# power_28V.net
KiCad netlist of a schematic drawn in Altium Designer
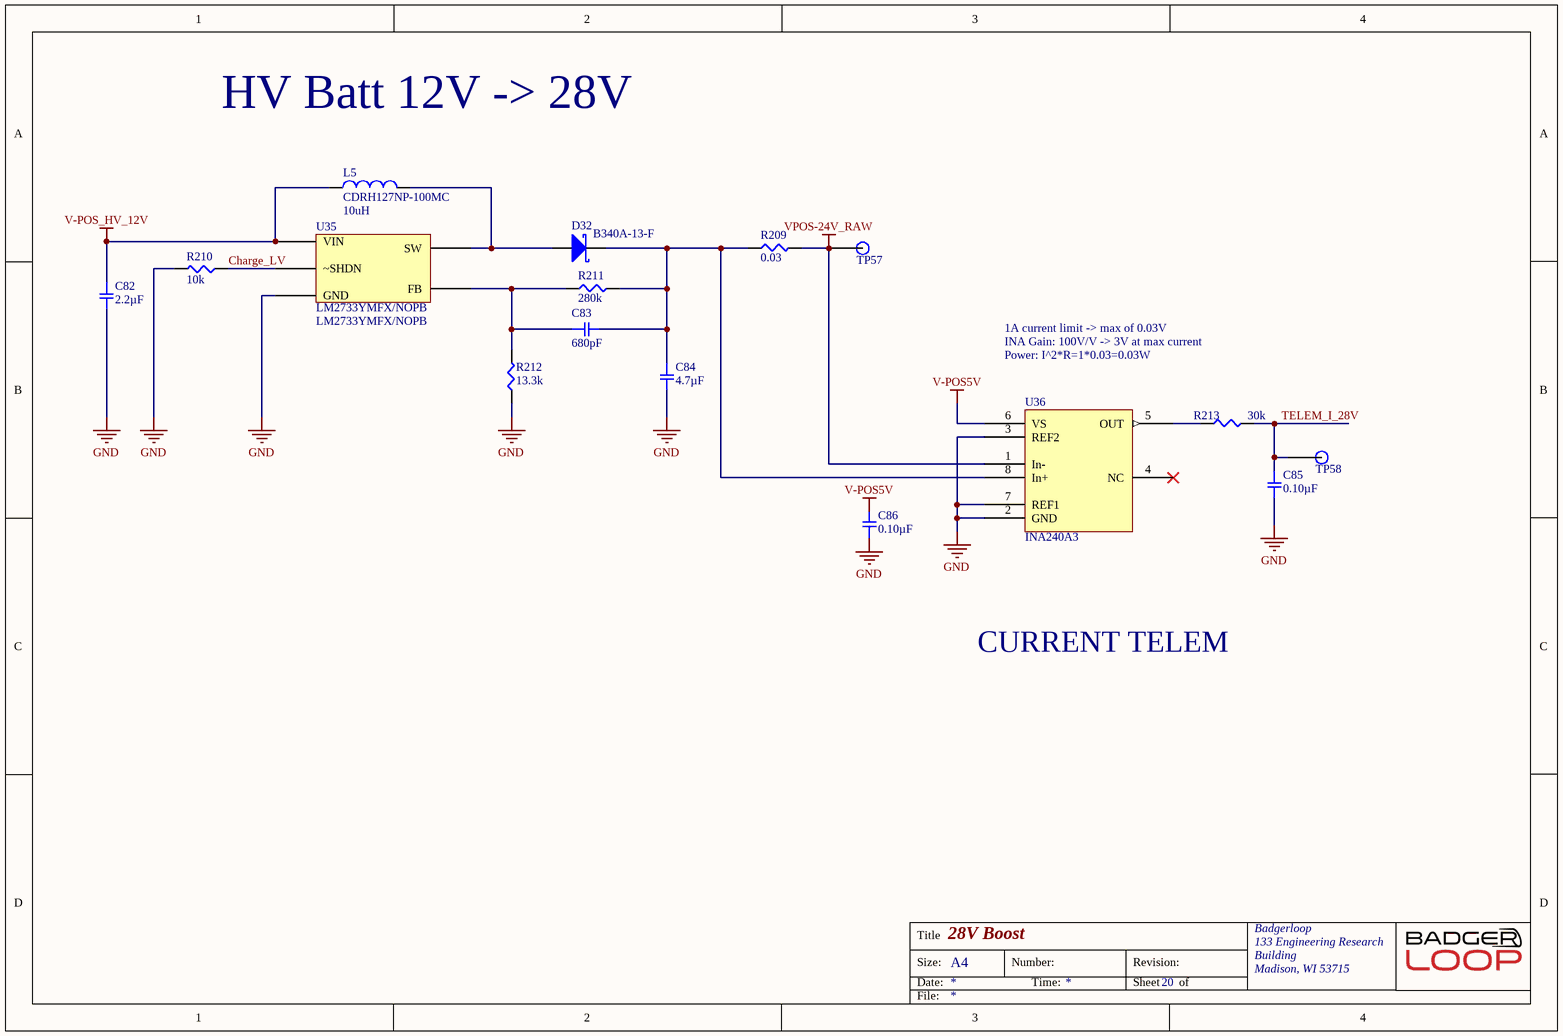
[diagram p0: power_28V.SchDoc]

(export (version "E")
  (design (tool "Eeschema 10.0.6"))
  (components
    (comp (ref "C82")
      (value "2.2µF")
      (footprint "SMD-1206C")
      (description "CAP CER 2.2UF 50V X6S 1206")
      (fields
        (field (name "DIGI-KEY PART NUMBER") "490-12422-1-ND")
        (field (name "PART NUMBER") "GRT31CC81H225KE01L")
      )
      (libsource (lib "capacitors") (part "GRT31CC81H225KE01L"))
    )
    (comp (ref "C83")
      (value "680pF")
      (footprint "SMD-0805C")
      (description "CAP CER 680PF 100V NP0 0805")
      (fields
        (field (name "DIGI-KEY PART NUMBER") "490-1613-1-ND")
        (field (name "PART NUMBER") "GRM2195C2A681JA01D")
      )
      (libsource (lib "capacitors") (part "GRM2195C2A681JA01D"))
    )
    (comp (ref "C84")
      (value "4.7µF")
      (footprint "SMD-1206C")
      (description "CAP CER 4.7UF 50V X7R 1206")
      (fields
        (field (name "DIGI-KEY PART NUMBER") "490-6521-1-ND")
        (field (name "PART NUMBER") "GRM31CR71H475KA12L")
      )
      (libsource (lib "capacitors") (part "GRM31CR71H475KA12L"))
    )
    (comp (ref "C85")
      (value "0.10µF")
      (footprint "SMD-0805C")
      (description "CAP CER 0.1UF 16V X7R 0805")
      (fields
        (field (name "DIGI-KEY PART NUMBER") "490-1683-1-ND")
        (field (name "PART NUMBER") "GRM219R71C104KA01D")
      )
      (libsource (lib "capacitors") (part "GRM219R71C104KA01D"))
    )
    (comp (ref "C86")
      (value "0.10µF")
      (footprint "SMD-0805C")
      (description "CAP CER 0.1UF 10V U2J 0805")
      (fields
        (field (name "DIGI-KEY PART NUMBER") "490-11592-1-ND")
        (field (name "PART NUMBER") "GRM21B7U1A104JA01L")
      )
      (libsource (lib "capacitors") (part "GRM21B7U1A104JA01L"))
    )
    (comp (ref "D32")
      (value "B340A-13-F")
      (footprint "DIOM4326X20N")
      (description "DIODE SCHOTTKY 40V 3A SMA")
      (fields (field (name "MANUFACTURER") "Diodes") (field (name "VOLTAGE") "40V"))
      (libsource (lib "misc") (part "B340A-13-F"))
    )
    (comp (ref "L5")
      (value "CDRH127NP-100MC")
      (footprint "INDP120120X80N")
      (description "Fixed Inductors 10uH 5.4A")
      (fields
        (field (name "MANUFACTURER") "Sumida")
        (field (name "TOLERANCE") "20%")
        (field (name "INDUCTANCE") "10uH")
      )
      (libsource (lib "inductor") (part "CDRH127NP-100MC"))
    )
    (comp (ref "R209")
      (value "0.03")
      (footprint "SMD-1206-RES")
      (description "RES SMD 0.03 OHM 1% 1W 1206")
      (fields
        (field (name "PART NUMBER") "ERJ-8CWFR030V")
        (field (name "DIGI-KEY PART NUMBER") "P0.03BVCT-ND")
      )
      (libsource (lib "resistors") (part "ERJ-8CWFR030V"))
    )
    (comp (ref "R210")
      (value "10k")
      (footprint "SMD-0805-RES")
      (description "RES SMD 10K OHM 5% 1/2W 0805")
      (fields (field (name "PART NUMBER") "ERJ-P06J103V") (field (name "DIGI-KEY PART NUMBER") "P10KADCT-ND"))
      (libsource (lib "resistors") (part "ERJ-P06J103V"))
    )
    (comp (ref "R211")
      (value "280k")
      (footprint "SMD-0805-RES")
      (description "RES SMD 280K OHM 1% 1/8W 0805")
      (fields
        (field (name "PART NUMBER") "ERJ-6ENF2803V")
        (field (name "DIGI-KEY PART NUMBER") "P280KCCT-ND")
      )
      (libsource (lib "resistors") (part "ERJ-6ENF2803V"))
    )
    (comp (ref "R212")
      (value "13.3k")
      (footprint "SMD-0805-RES")
      (description "RES SMD 13.3K OHM 1% 1/8W 0805")
      (fields
        (field (name "PART NUMBER") "ERJ-6ENF1332V")
        (field (name "DIGI-KEY PART NUMBER") "P13.3KCCT-ND")
      )
      (libsource (lib "resistors") (part "ERJ-6ENF1332V"))
    )
    (comp (ref "R213")
      (value "30k")
      (footprint "SMD-0805-RES")
      (description "RES SMD 30K OHM 1% 1/8W 0805")
      (fields
        (field (name "PART NUMBER") "ERJ-6ENF3002V")
        (field (name "DIGI-KEY PART NUMBER") "P30.0KCCT-ND")
      )
      (libsource (lib "resistors") (part "ERJ-6ENF3002V"))
    )
    (comp (ref "TP57")
      (value "TP")
      (footprint "Test Point")
      (description "SMD TEST POINT")
      (libsource (lib "misc") (part "TP"))
    )
    (comp (ref "TP58")
      (value "TP")
      (footprint "Test Point")
      (description "SMD TEST POINT")
      (libsource (lib "misc") (part "TP"))
    )
    (comp (ref "U35")
      (value "LM2733YMFX/NOPB")
      (footprint "TSOP95P280X145-6N")
      (description "Conv DC-DC Single Step Up 2.7V to 14V 5-Pin SOT-23 T/R")
      (fields
        (field (name "MANUFACTURER") "TI National Semiconductor")
        (field (name "MANUFACTURER PART NUMBER") "LM2733YMFX/NOPB")
      )
      (libsource (lib "ic") (part "LM2733YMFX/NOPB"))
    )
    (comp (ref "U36")
      (value "INA240A3")
      (footprint "SOIC127P600X175-8N")
      (description "IC AMP CURRENT SENSE 8-TSSOP 100V/V")
      (fields (field (name "MANUFACTURER") "Texas Instruments"))
      (libsource (lib "ic") (part "INA240A3"))
    )
  )
  (nets
    (net (code "1") (name "/Charge_LV") (class "Default")
      (node (ref "R210") (pin "1") (pinfunction "1_1") (pintype "passive"))
      (node (ref "U35") (pin "4") (pinfunction "~SHDN_4") (pintype "passive"))
    )
    (net (code "2") (name "/TELEM_I_28V") (class "Default")
      (node (ref "C85") (pin "1") (pinfunction "1_1") (pintype "passive"))
      (node (ref "R213") (pin "2") (pinfunction "2_2") (pintype "passive"))
      (node (ref "TP58") (pin "1") (pinfunction "1_1") (pintype "passive"))
    )
    (net (code "3") (name "GND") (class "Default")
      (node (ref "C82") (pin "2") (pinfunction "2_2") (pintype "passive"))
      (node (ref "C84") (pin "2") (pinfunction "2_2") (pintype "passive"))
      (node (ref "C85") (pin "2") (pinfunction "2_2") (pintype "passive"))
      (node (ref "C86") (pin "1") (pinfunction "1_1") (pintype "passive"))
      (node (ref "R210") (pin "2") (pinfunction "2_2") (pintype "passive"))
      (node (ref "R212") (pin "1") (pinfunction "1_1") (pintype "passive"))
      (node (ref "U35") (pin "2") (pinfunction "GND_2") (pintype "passive"))
      (node (ref "U36") (pin "2") (pinfunction "GND_2") (pintype "power_in"))
      (node (ref "U36") (pin "3") (pinfunction "REF2_3") (pintype "passive"))
      (node (ref "U36") (pin "7") (pinfunction "REF1_7") (pintype "passive"))
    )
    (net (code "4") (name "Net-(D32-A)") (class "Default")
      (node (ref "D32") (pin "2") (pinfunction "A_2") (pintype "passive"))
      (node (ref "L5") (pin "2") (pinfunction "2_2") (pintype "passive"))
      (node (ref "U35") (pin "1") (pinfunction "SW_1") (pintype "passive"))
    )
    (net (code "5") (name "Net-(D32-K)") (class "Default")
      (node (ref "C83") (pin "2") (pinfunction "2_2") (pintype "passive"))
      (node (ref "C84") (pin "1") (pinfunction "1_1") (pintype "passive"))
      (node (ref "D32") (pin "1") (pinfunction "K_1") (pintype "passive"))
      (node (ref "R209") (pin "1") (pinfunction "1_1") (pintype "passive"))
      (node (ref "R211") (pin "2") (pinfunction "2_2") (pintype "passive"))
      (node (ref "U36") (pin "8") (pinfunction "In+_8") (pintype "passive"))
    )
    (net (code "6") (name "Net-(U35-FB)") (class "Default")
      (node (ref "C83") (pin "1") (pinfunction "1_1") (pintype "passive"))
      (node (ref "R211") (pin "1") (pinfunction "1_1") (pintype "passive"))
      (node (ref "R212") (pin "2") (pinfunction "2_2") (pintype "passive"))
      (node (ref "U35") (pin "3") (pinfunction "FB_3") (pintype "passive"))
    )
    (net (code "7") (name "Net-(U36-OUT)") (class "Default")
      (node (ref "R213") (pin "1") (pinfunction "1_1") (pintype "passive"))
      (node (ref "U36") (pin "5") (pinfunction "OUT_5") (pintype "output"))
    )
    (net (code "8") (name "V-POS5V") (class "Default")
      (node (ref "C86") (pin "2") (pinfunction "2_2") (pintype "passive"))
      (node (ref "U36") (pin "6") (pinfunction "VS_6") (pintype "power_in"))
    )
    (net (code "9") (name "V-POS_HV_12V") (class "Default")
      (node (ref "C82") (pin "1") (pinfunction "1_1") (pintype "passive"))
      (node (ref "L5") (pin "1") (pinfunction "1_1") (pintype "passive"))
      (node (ref "U35") (pin "6") (pinfunction "VIN_6") (pintype "passive"))
    )
    (net (code "10") (name "VPOS-24V_RAW") (class "Default")
      (node (ref "R209") (pin "2") (pinfunction "2_2") (pintype "passive"))
      (node (ref "TP57") (pin "1") (pinfunction "1_1") (pintype "passive"))
      (node (ref "U36") (pin "1") (pinfunction "In-_1") (pintype "passive"))
    )
    (net (code "11") (name "unconnected-(U36-NC-Pad4)") (class "Default")
      (node (ref "U36") (pin "4") (pinfunction "NC_4") (pintype "passive+no_connect"))
    )
  )
)
